# Relay_via_transistor.net
KiCad netlist of a schematic drawn in Altium Designer
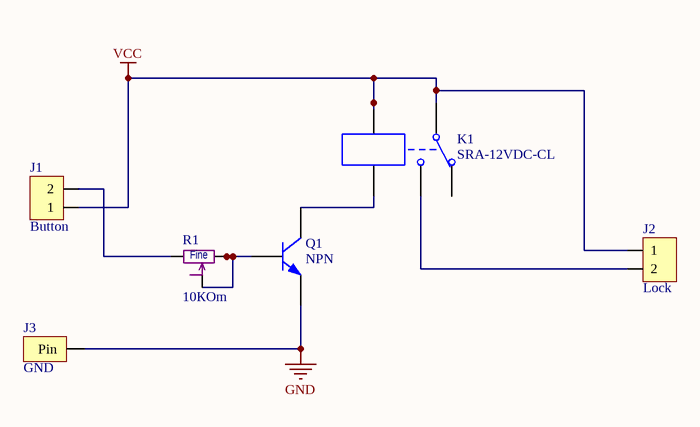
[diagram p0: Relay via transistor.SchDoc]

(export (version "E")
  (design (tool "Eeschema 10.0.6"))
  (components
    (comp (ref "J1")
      (value "Button")
      (footprint "Connector:Molex Micro-Fit 3.0 - 2 pin D R")
      (description "Horisontal, Dbl line, Male - 3mm")
      (fields (field (name "PART NUMBER") "430450200"))
      (libsource (lib "Connector") (part "Micro-Fit 2R (1x2)"))
    )
    (comp (ref "J2")
      (value "Lock")
      (footprint "Connector:Molex Micro-Fit 3.0 - 2 pin D R")
      (description "Horisontal, Dbl line, Male - 3mm")
      (fields (field (name "PART NUMBER") "430450200"))
      (libsource (lib "") (part "Micro-Fit 2R (1x2)_1"))
    )
    (comp (ref "J3")
      (value "GND")
      (footprint "Connector:OnePin 1.2x3")
      (description "Only pad")
      (libsource (lib "Connector") (part "OnePin Connector"))
    )
    (comp (ref "K1")
      (value "SRA-12VDC-CL")
      (footprint "Relay:SRA-12VDC-CL")
      (description "Single-Pole Dual-Throw Relay")
      (libsource (lib "Relay") (part "SRA-12VDC-CL"))
    )
    (comp (ref "Q1")
      (value "NPN")
      (footprint "GeneralCases:TO-92 2.54 (EBC)")
      (description "NPN Bipolar Transistor")
      (fields (field (name "PUBLISHER") "Altium Limited"))
      (libsource (lib "Transistor") (part "NPN"))
    )
    (comp (ref "R1")
      (value "10КOm")
      (footprint "PassiveComponents:Res Adj 3362P")
      (libsource (lib "PassiveComponents") (part "Res Adj 3362"))
    )
  )
  (nets
    (net (code "1") (name "GND") (class "Default")
      (node (ref "J3") (pin "1") (pinfunction "Pin_1") (pintype "passive"))
      (node (ref "Q1") (pin "E") (pinfunction "E_E") (pintype "passive"))
    )
    (net (code "2") (name "Net-(J1-Pad2)") (class "Default")
      (node (ref "J1") (pin "2") (pinfunction "2_2") (pintype "passive"))
      (node (ref "R1") (pin "1") (pinfunction "1_1") (pintype "passive"))
    )
    (net (code "3") (name "Net-(J2-Pad2)") (class "Default")
      (node (ref "J2") (pin "2") (pinfunction "2_2") (pintype "passive"))
      (node (ref "K1") (pin "3") (pinfunction "3_3") (pintype "passive"))
    )
    (net (code "4") (name "Net-(K1-Pad5)") (class "Default")
      (node (ref "K1") (pin "5") (pinfunction "5_5") (pintype "passive"))
      (node (ref "Q1") (pin "C") (pinfunction "C_C") (pintype "passive"))
    )
    (net (code "5") (name "Net-(Q1-PadB)") (class "Default")
      (node (ref "Q1") (pin "B") (pinfunction "B_B") (pintype "passive"))
      (node (ref "R1") (pin "2") (pinfunction "2_2") (pintype "passive"))
      (node (ref "R1") (pin "3") (pinfunction "3_3") (pintype "passive"))
    )
    (net (code "6") (name "VCC") (class "Default")
      (node (ref "J1") (pin "1") (pinfunction "1_1") (pintype "passive"))
      (node (ref "J2") (pin "1") (pinfunction "1_1") (pintype "passive"))
      (node (ref "K1") (pin "2") (pinfunction "2_2") (pintype "passive"))
      (node (ref "K1") (pin "4") (pinfunction "4_4") (pintype "passive"))
    )
    (net (code "7") (name "unconnected-(K1-Pad1)") (class "Default")
      (node (ref "K1") (pin "1") (pinfunction "1_1") (pintype "passive"))
    )
  )
)
